# Sheet1.net
KiCad netlist of a schematic drawn in Altium Designer
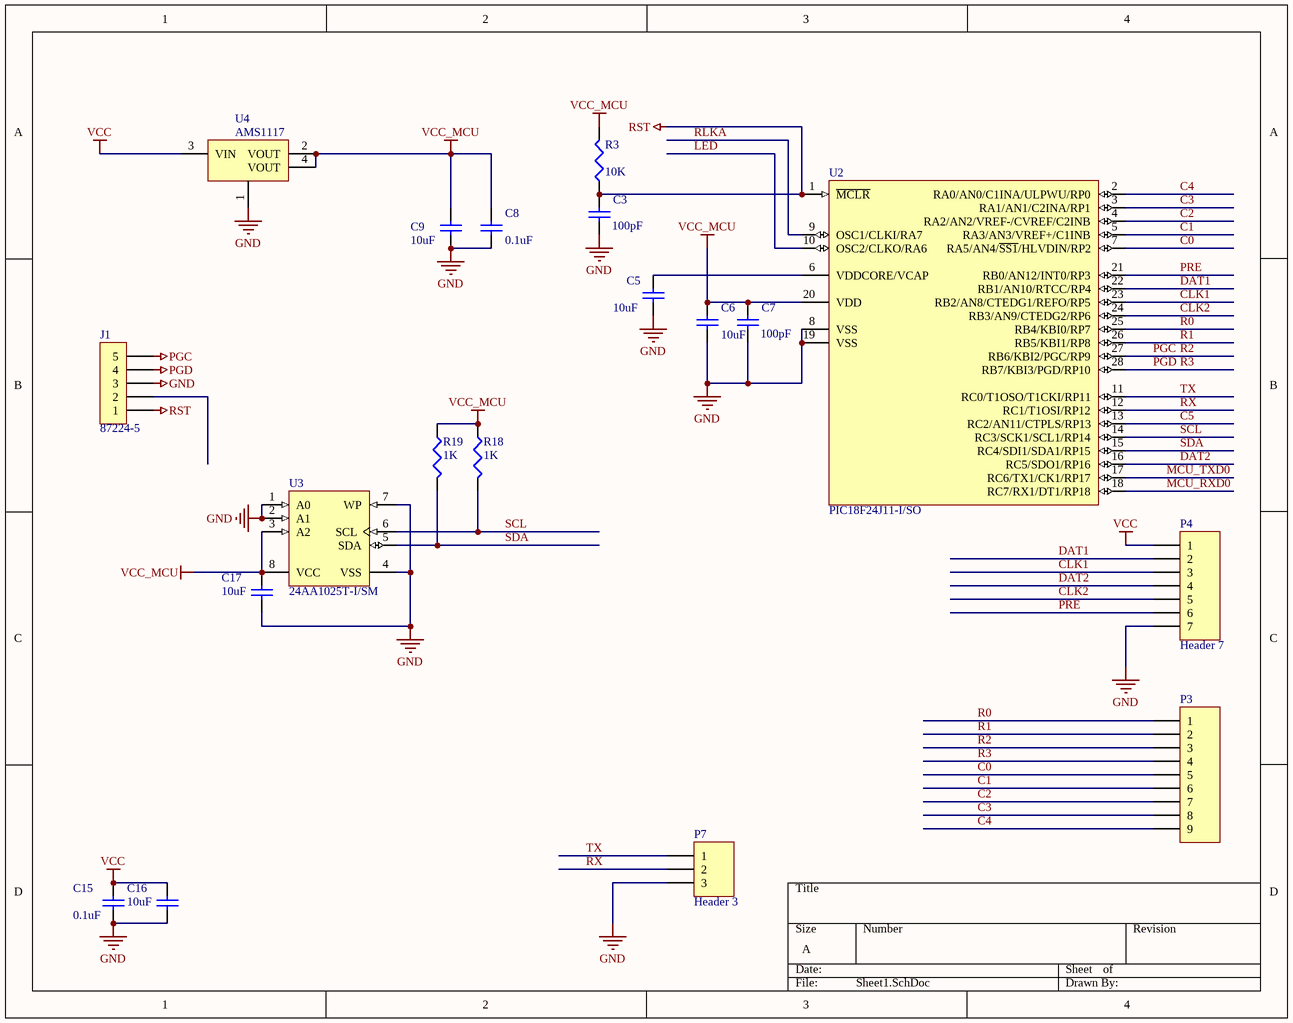
[diagram p0: Sheet1.SchDoc]

(export (version "E")
  (design (tool "Eeschema 10.0.6"))
  (components
    (comp (ref "C3")
      (value "100pF")
      (footprint "CAPC2013X05N")
      (description "Capacitor (Semiconductor SIM Model)")
      (fields (field (name "Comment") "Cap Semi") (field (name "PUBLISHER") "Altium Limited"))
      (libsource (lib "Miscellaneous Devices") (part "Cap Semi"))
    )
    (comp (ref "C5")
      (value "10uF")
      (footprint "CAPC2013X05N")
      (description "Capacitor (Semiconductor SIM Model)")
      (fields (field (name "Comment") "Cap Semi") (field (name "PUBLISHER") "Altium Limited"))
      (libsource (lib "Miscellaneous Devices") (part "Cap Semi"))
    )
    (comp (ref "C6")
      (value "10uF")
      (footprint "CAPC2013X05N")
      (description "Capacitor (Semiconductor SIM Model)")
      (fields (field (name "Comment") "Cap Semi") (field (name "PUBLISHER") "Altium Limited"))
      (libsource (lib "Miscellaneous Devices") (part "Cap Semi"))
    )
    (comp (ref "C7")
      (value "100pF")
      (footprint "CAPC2013X05N")
      (description "Capacitor (Semiconductor SIM Model)")
      (fields (field (name "Comment") "Cap Semi") (field (name "PUBLISHER") "Altium Limited"))
      (libsource (lib "Miscellaneous Devices") (part "Cap Semi"))
    )
    (comp (ref "C8")
      (value "0.1uF")
      (footprint "RESC2012L")
      (description "CAP CER 0.1UF 50V Y5V 0805")
      (fields (field (name "Comment") "CL21F104ZBCNNNC") (field (name "PUBLISHER") "Altium Limited"))
      (libsource (lib "Miscellaneous Devices") (part "Cap"))
    )
    (comp (ref "C9")
      (value "10uF")
      (footprint "RESC2012L")
      (description "CAP CER 10UF 10V Y5V 0805")
      (fields (field (name "Comment") "LMK212F106ZG-T") (field (name "PUBLISHER") "Altium Limited"))
      (libsource (lib "Miscellaneous Devices") (part "Cap"))
    )
    (comp (ref "C15")
      (value "0.1uF")
      (footprint "RESC2012L")
      (description "CAP CER 0.1UF 50V Y5V 0805")
      (fields (field (name "Comment") "CL21F104ZBCNNNC") (field (name "PUBLISHER") "Altium Limited"))
      (libsource (lib "Miscellaneous Devices") (part "Cap"))
    )
    (comp (ref "C16")
      (value "10uF")
      (footprint "RESC2012L")
      (description "CAP CER 10UF 10V Y5V 0805")
      (fields (field (name "Comment") "LMK212F106ZG-T") (field (name "PUBLISHER") "Altium Limited"))
      (libsource (lib "Miscellaneous Devices") (part "Cap"))
    )
    (comp (ref "C17")
      (value "10uF")
      (footprint "RESC2012L")
      (description "CAP CER 10UF 10V Y5V 0805")
      (fields (field (name "Comment") "LMK212F106ZG-T") (field (name "PUBLISHER") "Altium Limited"))
      (libsource (lib "Miscellaneous Devices") (part "Cap"))
    )
    (comp (ref "J1")
      (value "87224-5")
      (footprint "CON5")
      (description "CONN HEADER VERT .100 5POS 15AU")
      (libsource (lib "*") (part "CON5"))
    )
    (comp (ref "P3")
      (value "Header 9")
      (footprint "HDR1X9")
      (description "Header, 9-Pin")
      (fields (field (name "PUBLISHER") "Altium Limited"))
      (libsource (lib "Miscellaneous Connectors") (part "Header 9"))
    )
    (comp (ref "P4")
      (value "Header 7")
      (footprint "HDR1X7")
      (description "Header, 7-Pin")
      (fields (field (name "PUBLISHER") "Altium Limited"))
      (libsource (lib "Miscellaneous Connectors") (part "Header 7"))
    )
    (comp (ref "P7")
      (value "Header 3")
      (footprint "HDR1X3")
      (description "Header, 3-Pin")
      (fields (field (name "PUBLISHER") "Altium Limited"))
      (libsource (lib "Miscellaneous Connectors") (part "Header 3"))
    )
    (comp (ref "R3")
      (value "10K")
      (footprint "RESC2013X05N")
      (description "Resistor")
      (fields (field (name "Comment") "Res3") (field (name "PUBLISHER") "Altium Limited"))
      (libsource (lib "Miscellaneous Devices") (part "Res3"))
    )
    (comp (ref "R18")
      (value "1K")
      (footprint "RESC2012L")
      (description "RES 330 OHM 1/8W 5% 0805 SMD")
      (fields (field (name "Comment") "ERJ-6GEYJ331V") (field (name "PUBLISHER") "Altium Limited"))
      (libsource (lib "Miscellaneous Devices") (part "Res3"))
    )
    (comp (ref "R19")
      (value "1K")
      (footprint "RESC2012L")
      (description "RES 330 OHM 1/8W 5% 0805 SMD")
      (fields (field (name "Comment") "ERJ-6GEYJ331V") (field (name "PUBLISHER") "Altium Limited"))
      (libsource (lib "Miscellaneous Devices") (part "Res3"))
    )
    (comp (ref "U2")
      (value "PIC18F24J11-I/SO")
      (footprint "SOIC-SO28_N")
      (fields (field (name "PUBLISHER") "Altium Limited"))
      (libsource (lib "Microchip Microcontroller 8-Bit PIC18") (part "PIC18F24J11-I/SO"))
    )
    (comp (ref "U3")
      (value "24AA1025T-I/SM")
      (footprint "SOIJ-SM8_N")
      (description "1 Mbit, 400kHz, 1.7V, I2C Serial EEPROM, 8-Pin SOIC 208mil, Industrial Temperature, Tape and Reel")
      (fields (field (name "PUBLISHER") "Altium Limited"))
      (libsource (lib "Microchip Memory I2C Serial EEPROM") (part "24AA1025T-I/SM"))
    )
    (comp (ref "U4")
      (value "AMS1117")
      (footprint "SOT223-4M")
      (description "Adjustable Precision Shunt Regulator")
      (fields (field (name "PUBLISHER") "Altium Limited"))
      (libsource (lib "Schlib1") (part "AMS1117"))
    )
  )
  (nets
    (net (code "1") (name "/C0") (class "Default")
      (node (ref "P3") (pin "5") (pinfunction "5_5") (pintype "passive"))
      (node (ref "U2") (pin "7") (pinfunction "RA5/AN4/~{SS1}/HLVDIN/RP2_7") (pintype "bidirectional"))
    )
    (net (code "2") (name "/C1") (class "Default")
      (node (ref "P3") (pin "6") (pinfunction "6_6") (pintype "passive"))
      (node (ref "U2") (pin "5") (pinfunction "RA3/AN3/VREF+/C1INB_5") (pintype "bidirectional"))
    )
    (net (code "3") (name "/C2") (class "Default")
      (node (ref "P3") (pin "7") (pinfunction "7_7") (pintype "passive"))
      (node (ref "U2") (pin "4") (pinfunction "RA2/AN2/VREF-/CVREF/C2INB_4") (pintype "bidirectional"))
    )
    (net (code "4") (name "/C3") (class "Default")
      (node (ref "P3") (pin "8") (pinfunction "8_8") (pintype "passive"))
      (node (ref "U2") (pin "3") (pinfunction "RA1/AN1/C2INA/RP1_3") (pintype "bidirectional"))
    )
    (net (code "5") (name "/C4") (class "Default")
      (node (ref "P3") (pin "9") (pinfunction "9_9") (pintype "passive"))
      (node (ref "U2") (pin "2") (pinfunction "RA0/AN0/C1INA/ULPWU/RP0_2") (pintype "bidirectional"))
    )
    (net (code "6") (name "/C5") (class "Default")
      (node (ref "U2") (pin "13") (pinfunction "RC2/AN11/CTPLS/RP13_13") (pintype "bidirectional"))
    )
    (net (code "7") (name "/CLK1") (class "Default")
      (node (ref "P4") (pin "3") (pinfunction "3_3") (pintype "passive"))
      (node (ref "U2") (pin "23") (pinfunction "RB2/AN8/CTEDG1/REFO/RP5_23") (pintype "bidirectional"))
    )
    (net (code "8") (name "/CLK2") (class "Default")
      (node (ref "P4") (pin "5") (pinfunction "5_5") (pintype "passive"))
      (node (ref "U2") (pin "24") (pinfunction "RB3/AN9/CTEDG2/RP6_24") (pintype "bidirectional"))
    )
    (net (code "9") (name "/DAT1") (class "Default")
      (node (ref "P4") (pin "2") (pinfunction "2_2") (pintype "passive"))
      (node (ref "U2") (pin "22") (pinfunction "RB1/AN10/RTCC/RP4_22") (pintype "bidirectional"))
    )
    (net (code "10") (name "/DAT2") (class "Default")
      (node (ref "P4") (pin "4") (pinfunction "4_4") (pintype "passive"))
      (node (ref "U2") (pin "16") (pinfunction "RC5/SDO1/RP16_16") (pintype "bidirectional"))
    )
    (net (code "11") (name "/LED") (class "Default")
      (node (ref "U2") (pin "10") (pinfunction "OSC2/CLKO/RA6_10") (pintype "bidirectional"))
    )
    (net (code "12") (name "/MCU_RXD0") (class "Default")
      (node (ref "U2") (pin "18") (pinfunction "RC7/RX1/DT1/RP18_18") (pintype "bidirectional"))
    )
    (net (code "13") (name "/MCU_TXD0") (class "Default")
      (node (ref "U2") (pin "17") (pinfunction "RC6/TX1/CK1/RP17_17") (pintype "bidirectional"))
    )
    (net (code "14") (name "/PRE") (class "Default")
      (node (ref "P4") (pin "6") (pinfunction "6_6") (pintype "passive"))
      (node (ref "U2") (pin "21") (pinfunction "RB0/AN12/INT0/RP3_21") (pintype "bidirectional"))
    )
    (net (code "15") (name "/R0") (class "Default")
      (node (ref "P3") (pin "1") (pinfunction "1_1") (pintype "passive"))
      (node (ref "U2") (pin "25") (pinfunction "RB4/KBI0/RP7_25") (pintype "bidirectional"))
    )
    (net (code "16") (name "/R1") (class "Default")
      (node (ref "P3") (pin "2") (pinfunction "2_2") (pintype "passive"))
      (node (ref "U2") (pin "26") (pinfunction "RB5/KBI1/RP8_26") (pintype "bidirectional"))
    )
    (net (code "17") (name "/RLKA") (class "Default")
      (node (ref "U2") (pin "9") (pinfunction "OSC1/CLKI/RA7_9") (pintype "bidirectional"))
    )
    (net (code "18") (name "/RX") (class "Default")
      (node (ref "P7") (pin "2") (pinfunction "2_2") (pintype "passive"))
      (node (ref "U2") (pin "12") (pinfunction "RC1/T1OSI/RP12_12") (pintype "bidirectional"))
    )
    (net (code "19") (name "/SCL") (class "Default")
      (node (ref "R18") (pin "1") (pinfunction "1_1") (pintype "passive"))
      (node (ref "U2") (pin "14") (pinfunction "RC3/SCK1/SCL1/RP14_14") (pintype "bidirectional"))
      (node (ref "U3") (pin "6") (pinfunction "SCL_6") (pintype "input"))
    )
    (net (code "20") (name "/SDA") (class "Default")
      (node (ref "R19") (pin "1") (pinfunction "1_1") (pintype "passive"))
      (node (ref "U2") (pin "15") (pinfunction "RC4/SDI1/SDA1/RP15_15") (pintype "bidirectional"))
      (node (ref "U3") (pin "5") (pinfunction "SDA_5") (pintype "bidirectional"))
    )
    (net (code "21") (name "/TX") (class "Default")
      (node (ref "P7") (pin "1") (pinfunction "1_1") (pintype "passive"))
      (node (ref "U2") (pin "11") (pinfunction "RC0/T1OSO/T1CKI/RP11_11") (pintype "bidirectional"))
    )
    (net (code "22") (name "GND") (class "Default")
      (node (ref "C15") (pin "2") (pinfunction "2_2") (pintype "passive"))
      (node (ref "C16") (pin "2") (pinfunction "2_2") (pintype "passive"))
      (node (ref "C17") (pin "2") (pinfunction "2_2") (pintype "passive"))
      (node (ref "C3") (pin "1") (pinfunction "1_1") (pintype "passive"))
      (node (ref "C5") (pin "1") (pinfunction "1_1") (pintype "passive"))
      (node (ref "C6") (pin "1") (pinfunction "1_1") (pintype "passive"))
      (node (ref "C7") (pin "1") (pinfunction "1_1") (pintype "passive"))
      (node (ref "C8") (pin "2") (pinfunction "2_2") (pintype "passive"))
      (node (ref "C9") (pin "2") (pinfunction "2_2") (pintype "passive"))
      (node (ref "J1") (pin "3") (pinfunction "3_3") (pintype "passive"))
      (node (ref "P4") (pin "7") (pinfunction "7_7") (pintype "passive"))
      (node (ref "P7") (pin "3") (pinfunction "3_3") (pintype "passive"))
      (node (ref "U2") (pin "19") (pinfunction "VSS_19") (pintype "power_in"))
      (node (ref "U2") (pin "8") (pinfunction "VSS_8") (pintype "power_in"))
      (node (ref "U3") (pin "1") (pinfunction "A0_1") (pintype "input"))
      (node (ref "U3") (pin "2") (pinfunction "A1_2") (pintype "input"))
      (node (ref "U3") (pin "4") (pinfunction "VSS_4") (pintype "power_in"))
      (node (ref "U3") (pin "7") (pinfunction "WP_7") (pintype "input"))
      (node (ref "U4") (pin "1") (pinfunction "GND_1") (pintype "power_in"))
    )
    (net (code "23") (name "Net-(U2-VDDCORE{slash}VCAP)") (class "Default")
      (node (ref "C5") (pin "2") (pinfunction "2_2") (pintype "passive"))
      (node (ref "U2") (pin "6") (pinfunction "VDDCORE/VCAP_6") (pintype "power_in"))
    )
    (net (code "24") (name "PGC") (class "Default")
      (node (ref "J1") (pin "5") (pinfunction "5_5") (pintype "passive"))
      (node (ref "P3") (pin "3") (pinfunction "3_3") (pintype "passive"))
      (node (ref "U2") (pin "27") (pinfunction "RB6/KBI2/PGC/RP9_27") (pintype "bidirectional"))
    )
    (net (code "25") (name "PGD") (class "Default")
      (node (ref "J1") (pin "4") (pinfunction "4_4") (pintype "passive"))
      (node (ref "P3") (pin "4") (pinfunction "4_4") (pintype "passive"))
      (node (ref "U2") (pin "28") (pinfunction "RB7/KBI3/PGD/RP10_28") (pintype "bidirectional"))
    )
    (net (code "26") (name "RST") (class "Default")
      (node (ref "C3") (pin "2") (pinfunction "2_2") (pintype "passive"))
      (node (ref "J1") (pin "1") (pinfunction "1_1") (pintype "passive"))
      (node (ref "R3") (pin "1") (pinfunction "1_1") (pintype "passive"))
      (node (ref "U2") (pin "1") (pinfunction "~{MCLR}_1") (pintype "input"))
    )
    (net (code "27") (name "VCC") (class "Default")
      (node (ref "C15") (pin "1") (pinfunction "1_1") (pintype "passive"))
      (node (ref "C16") (pin "1") (pinfunction "1_1") (pintype "passive"))
      (node (ref "P4") (pin "1") (pinfunction "1_1") (pintype "passive"))
      (node (ref "U4") (pin "3") (pinfunction "VIN_3") (pintype "power_in"))
    )
    (net (code "28") (name "VCC_MCU") (class "Default")
      (node (ref "C17") (pin "1") (pinfunction "1_1") (pintype "passive"))
      (node (ref "C6") (pin "2") (pinfunction "2_2") (pintype "passive"))
      (node (ref "C7") (pin "2") (pinfunction "2_2") (pintype "passive"))
      (node (ref "C8") (pin "1") (pinfunction "1_1") (pintype "passive"))
      (node (ref "C9") (pin "1") (pinfunction "1_1") (pintype "passive"))
      (node (ref "R18") (pin "2") (pinfunction "2_2") (pintype "passive"))
      (node (ref "R19") (pin "2") (pinfunction "2_2") (pintype "passive"))
      (node (ref "R3") (pin "2") (pinfunction "2_2") (pintype "passive"))
      (node (ref "U2") (pin "20") (pinfunction "VDD_20") (pintype "power_in"))
      (node (ref "U3") (pin "3") (pinfunction "A2_3") (pintype "input"))
      (node (ref "U3") (pin "8") (pinfunction "VCC_8") (pintype "power_in"))
      (node (ref "U4") (pin "2") (pinfunction "VOUT_2") (pintype "power_in"))
      (node (ref "U4") (pin "4") (pinfunction "VOUT_4") (pintype "power_in"))
    )
    (net (code "29") (name "unconnected-(J1-Pad2)") (class "Default")
      (node (ref "J1") (pin "2") (pinfunction "2_2") (pintype "passive"))
    )
  )
)
